# LC_LPF4.net
KiCad netlist of a schematic drawn in Altium Designer
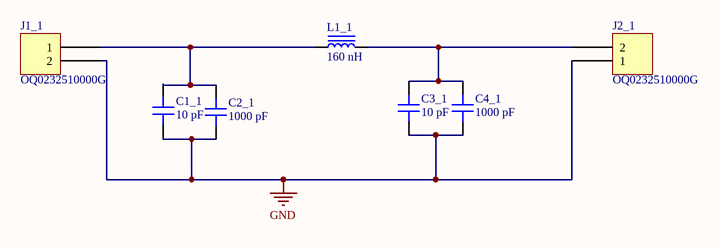
[diagram p0: LC_LPF4.SchDoc]

(export (version "E")
  (design (tool "Eeschema 10.0.6"))
  (components
    (comp (ref "C1_1")
      (value "10 pF")
      (footprint "CAP 0603_1608")
      (description "CAP CER 10PF 100V C0G/NPO 0603")
      (fields (field (name "PART NUMBER") "AC0603JRNPO0BN100") (field (name "MANUFACTURER") "Yageo"))
      (libsource (lib "Celestial Altium Library - altium_library") (part "Capacitor"))
    )
    (comp (ref "C2_1")
      (value "1000 pF")
      (footprint "CAP 0603_1608")
      (description "CAP CER 1000PF 100V X7R 0603")
      (fields
        (field (name "PART NUMBER") "GCD188R72A102KA01D")
        (field (name "MANUFACTURER") "Murata Electronics")
      )
      (libsource (lib "Celestial Altium Library - altium_library") (part "Capacitor"))
    )
    (comp (ref "C3_1")
      (value "10 pF")
      (footprint "CAP 0603_1608")
      (description "CAP CER 10PF 100V C0G/NPO 0603")
      (fields (field (name "PART NUMBER") "AC0603JRNPO0BN100") (field (name "MANUFACTURER") "Yageo"))
      (libsource (lib "Celestial Altium Library - altium_library") (part "Capacitor"))
    )
    (comp (ref "C4_1")
      (value "1000 pF")
      (footprint "CAP 0603_1608")
      (description "CAP CER 1000PF 100V X7R 0603")
      (fields
        (field (name "PART NUMBER") "GCD188R72A102KA01D")
        (field (name "MANUFACTURER") "Murata Electronics")
      )
      (libsource (lib "Celestial Altium Library - altium_library") (part "Capacitor"))
    )
    (comp (ref "J1_1")
      (value "OQ0232510000G")
      (footprint "FCI 06-381-2PIN")
      (description "TERM BLOCK HDR 2POS 90DEG 3.81MM")
      (fields (field (name "MANUFACTURER") "Amphenol Anytek"))
      (libsource (lib "") (part "2 Pin_1"))
    )
    (comp (ref "J2_1")
      (value "OQ0232510000G")
      (footprint "FCI 06-381-2PIN")
      (description "TERM BLOCK HDR 2POS 90DEG 3.81MM")
      (fields (field (name "MANUFACTURER") "Amphenol Anytek"))
      (libsource (lib "Celestial Altium Library - altium_library") (part "2 Pin"))
    )
    (comp (ref "L1_1")
      (value "160 nH")
      (footprint "IND 0402_1005 RF WW")
      (description "FIXED IND 160NH 480MA 330MOHM SM")
      (fields
        (field (name "PART NUMBER") "LQW15CNR16J00D")
        (field (name "MANUFACTURER") "Murata Electronics")
      )
      (libsource (lib "Celestial Altium Library - altium_library") (part "Inductor"))
    )
  )
  (nets
    (net (code "1") (name "GND") (class "Default")
      (node (ref "C1_1") (pin "1") (pinfunction "1_1") (pintype "passive"))
      (node (ref "C2_1") (pin "2") (pinfunction "2_2") (pintype "passive"))
      (node (ref "C3_1") (pin "1") (pinfunction "1_1") (pintype "passive"))
      (node (ref "C4_1") (pin "2") (pinfunction "2_2") (pintype "passive"))
      (node (ref "J1_1") (pin "2") (pinfunction "2_2") (pintype "passive"))
      (node (ref "J2_1") (pin "1") (pinfunction "1_1") (pintype "passive"))
    )
    (net (code "2") (name "Net-(C1_1-Pad2)") (class "Default")
      (node (ref "C1_1") (pin "2") (pinfunction "2_2") (pintype "passive"))
      (node (ref "C2_1") (pin "1") (pinfunction "1_1") (pintype "passive"))
      (node (ref "J1_1") (pin "1") (pinfunction "1_1") (pintype "passive"))
      (node (ref "L1_1") (pin "1") (pinfunction "1_1") (pintype "passive"))
    )
    (net (code "3") (name "Net-(C3_1-Pad2)") (class "Default")
      (node (ref "C3_1") (pin "2") (pinfunction "2_2") (pintype "passive"))
      (node (ref "C4_1") (pin "1") (pinfunction "1_1") (pintype "passive"))
      (node (ref "J2_1") (pin "2") (pinfunction "2_2") (pintype "passive"))
      (node (ref "L1_1") (pin "2") (pinfunction "2_2") (pintype "passive"))
    )
  )
)
